# power.net
KiCad netlist of a schematic drawn in Altium Designer
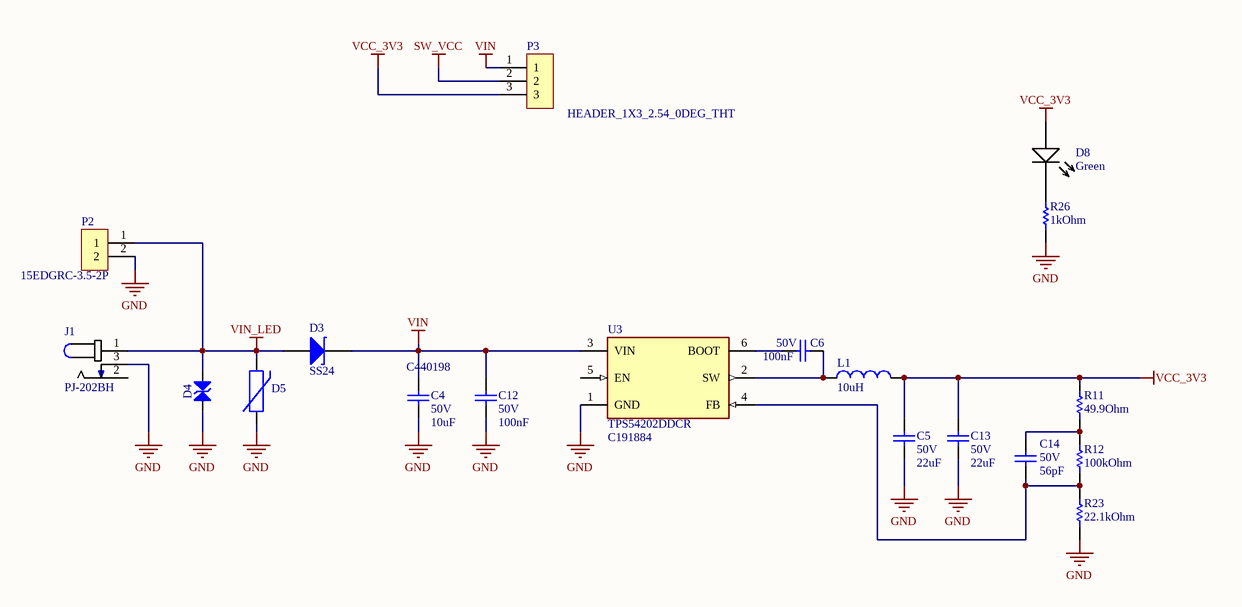
[diagram p0: power.SchDoc]

(export (version "E")
  (design (tool "Eeschema 10.0.6"))
  (components
    (comp (ref "C4")
      (value "10uF 0805 50V")
      (footprint "CAP_0805_High_density")
      (description "Generic Ceramic Capacitor SMD")
      (fields
        (field (name "TOLERANCE") "0%")
        (field (name "VOLTAGE") "50V")
        (field (name "CAPACITANCE") "10uF")
        (field (name "SUPPLIER PART NUMBER 1") "C440198")
      )
      (libsource (lib "MY_LIB") (part "Capacitor SMD_1"))
    )
    (comp (ref "C5")
      (value "22uF 0805 50V")
      (footprint "CAP_0805_High_density")
      (description "Generic Ceramic Capacitor SMD")
      (fields
        (field (name "TOLERANCE") "0%")
        (field (name "VOLTAGE") "50V")
        (field (name "CAPACITANCE") "22uF")
      )
      (libsource (lib "MY_LIB") (part "Capacitor SMD_1"))
    )
    (comp (ref "C6")
      (value "~")
      (footprint "CAP_0603_High_density")
      (description "Generic Ceramic Capacitor SMD")
      (fields
        (field (name "TOLERANCE") "10%")
        (field (name "VOLTAGE") "50V")
        (field (name "CAPACITANCE") "100nF")
      )
      (libsource (lib "altium_conclusive_library") (part "Capacitor SMD"))
    )
    (comp (ref "C12")
      (value "~")
      (footprint "CAP_0603_High_density")
      (description "Generic Ceramic Capacitor SMD")
      (fields
        (field (name "TOLERANCE") "10%")
        (field (name "VOLTAGE") "50V")
        (field (name "CAPACITANCE") "100nF")
      )
      (libsource (lib "altium_conclusive_library") (part "Capacitor SMD"))
    )
    (comp (ref "C13")
      (value "22uF 0805 50V")
      (footprint "CAP_0805_High_density")
      (description "Generic Ceramic Capacitor SMD")
      (fields
        (field (name "TOLERANCE") "0%")
        (field (name "VOLTAGE") "50V")
        (field (name "CAPACITANCE") "22uF")
      )
      (libsource (lib "MY_LIB") (part "Capacitor SMD_1"))
    )
    (comp (ref "C14")
      (value "56pF 0603 50V")
      (footprint "CAP_0603_High_density")
      (description "Generic Ceramic Capacitor SMD")
      (fields
        (field (name "TOLERANCE") "0%")
        (field (name "VOLTAGE") "50V")
        (field (name "CAPACITANCE") "56pF")
      )
      (libsource (lib "MY_LIB") (part "Capacitor SMD_1"))
    )
    (comp (ref "D3")
      (value "SS24")
      (footprint "DO214AA")
      (description "40V Single 500mV@2A 2A DO-214AA Schottky Barrier Diodes (SBD) ROHS")
      (libsource (lib "MY_LIB") (part "Dioda prostownicza Schottky"))
    )
    (comp (ref "D4")
      (value "SMCJ15CA")
      (footprint "DIOM7959X262N")
      (description "24.4V Clamp 61.5A Ipp Tvs Diode Surface Mount DO-214AB (SMCJ)")
      (fields
        (field (name "PART NUMBER") "SMCJ28CA")
        (field (name "VOLTAGE") "28V")
        (field (name "AUTHOR") "CERN DEM JLC")
      )
      (libsource (lib "altium_conclusive_library") (part "SMCJ15CA"))
    )
    (comp (ref "D5")
      (value "C283933")
      (footprint "SIOV-S14K50")
      (description "82V 4.5kA Varistor 1 Circuit Through Hole Disc 14mm")
      (libsource (lib "altium_conclusive_library") (part "B72214S0500K101"))
    )
    (comp (ref "D8")
      (value "C205450")
      (footprint "LED_0603")
      (description "Generic LED diode SMD Green")
      (fields (field (name "COLOUR") "Green"))
      (libsource (lib "MY_LIB") (part "LED diode"))
    )
    (comp (ref "J1")
      (value "PJ-202BH")
      (footprint "CUI_PJ-202BH")
      (description "2.5 x 6.5 mm, 5.0 A, Horizontal, Through Hole, Kinked Pins, Dc Power Jack Connector")
      (libsource (lib "altium_conclusive_library") (part "PJ-202BH"))
    )
    (comp (ref "L1")
      (value "NR8040T100M")
      (footprint "INDP8080X42N")
      (description "10µH Shielded Wirewound Inductor 3.1A 44.2mOhm Max Nonstandard")
      (fields (field (name "INDUCTANCE") "10uH"))
      (libsource (lib "MY_LIB") (part "NR8040T100M"))
    )
    (comp (ref "P2")
      (value "15EDGRC-3.5-2P")
      (footprint "15EDGRC-3.5 - 2 pin")
      (description "15EDGRC-3.5 - 2 pin")
      (libsource (lib "MY_LIB") (part "15EDGRC-3.5-2P"))
    )
    (comp (ref "P3")
      (value "HEADER_1X3_2.54_0DEG_THT")
      (footprint "HDR1X3_2.54")
      (description "3pin 1x3 2.54mm 0.100\" pitch header vertical tht")
      (libsource (lib "MY_LIB") (part "Header 1x3"))
    )
    (comp (ref "R11")
      (value "0603 49.9Ohm 1%")
      (footprint "RES_0603")
      (description "Generic Resistor SMD")
      (fields (field (name "RESISTANCE") "49.9Ohm"))
      (libsource (lib "MY_LIB") (part "Resistor SMD_1"))
    )
    (comp (ref "R12")
      (value "0603 100kOhm 1%")
      (footprint "RES_0603")
      (description "Generic Resistor SMD")
      (fields (field (name "RESISTANCE") "100kOhm"))
      (libsource (lib "MY_LIB") (part "Resistor SMD_1"))
    )
    (comp (ref "R23")
      (value "0603 22.1kOhm 1%")
      (footprint "RES_0603")
      (description "Generic Resistor SMD")
      (fields (field (name "RESISTANCE") "22.1kOhm"))
      (libsource (lib "MY_LIB") (part "Resistor SMD_1"))
    )
    (comp (ref "R26")
      (value "0603 1kOhm 1%")
      (footprint "RES_0603")
      (description "Generic Resistor SMD")
      (fields (field (name "RESISTANCE") "1kOhm"))
      (libsource (lib "MY_LIB") (part "Resistor SMD_1"))
    )
    (comp (ref "U3")
      (value "TPS54202DDCR")
      (footprint "FP-DDC0006A-MFG")
      (description "IC REG BUCK ADJ 2A TSOT23-6")
      (fields (field (name "SUPPLIER PART NUMBER 1") "C191884"))
      (libsource (lib "MY_LIB") (part "TPS54202DDCR"))
    )
  )
  (nets
    (net (code "1") (name "GND") (class "Default")
      (node (ref "C12") (pin "2") (pinfunction "2_2") (pintype "passive"))
      (node (ref "C13") (pin "1") (pinfunction "1_1") (pintype "passive"))
      (node (ref "C4") (pin "1") (pinfunction "1_1") (pintype "passive"))
      (node (ref "C5") (pin "1") (pinfunction "1_1") (pintype "passive"))
      (node (ref "D4") (pin "2") (pinfunction "A_2") (pintype "passive"))
      (node (ref "D5") (pin "1") (pinfunction "1_1") (pintype "passive"))
      (node (ref "J1") (pin "3") (pinfunction "3_3") (pintype "passive"))
      (node (ref "P2") (pin "2") (pinfunction "2_2") (pintype "passive"))
      (node (ref "R23") (pin "2") (pinfunction "2_2") (pintype "passive"))
      (node (ref "R26") (pin "1") (pinfunction "1_1") (pintype "passive"))
      (node (ref "U3") (pin "1") (pinfunction "GND_1") (pintype "power_in"))
    )
    (net (code "2") (name "Net-(C14-Pad2)") (class "Default")
      (node (ref "C14") (pin "2") (pinfunction "2_2") (pintype "passive"))
      (node (ref "R11") (pin "2") (pinfunction "2_2") (pintype "passive"))
      (node (ref "R12") (pin "1") (pinfunction "1_1") (pintype "passive"))
    )
    (net (code "3") (name "Net-(D8-PadC)") (class "Default")
      (node (ref "D8") (pin "C") (pinfunction "C_C") (pintype "passive"))
      (node (ref "R26") (pin "2") (pinfunction "2_2") (pintype "passive"))
    )
    (net (code "4") (name "Net-(U3-BOOT)") (class "Default")
      (node (ref "C6") (pin "1") (pinfunction "1_1") (pintype "passive"))
      (node (ref "U3") (pin "6") (pinfunction "BOOT_6") (pintype "passive"))
    )
    (net (code "5") (name "Net-(U3-FB)") (class "Default")
      (node (ref "C14") (pin "1") (pinfunction "1_1") (pintype "passive"))
      (node (ref "R12") (pin "2") (pinfunction "2_2") (pintype "passive"))
      (node (ref "R23") (pin "1") (pinfunction "1_1") (pintype "passive"))
      (node (ref "U3") (pin "4") (pinfunction "FB_4") (pintype "input"))
    )
    (net (code "6") (name "Net-(U3-SW)") (class "Default")
      (node (ref "C6") (pin "2") (pinfunction "2_2") (pintype "passive"))
      (node (ref "L1") (pin "1") (pinfunction "1_1") (pintype "passive"))
      (node (ref "U3") (pin "2") (pinfunction "SW_2") (pintype "output"))
    )
    (net (code "7") (name "SW_VCC") (class "Default")
      (node (ref "P3") (pin "2") (pinfunction "2_2") (pintype "passive"))
    )
    (net (code "8") (name "VCC_3V3") (class "Default")
      (node (ref "C13") (pin "2") (pinfunction "2_2") (pintype "passive"))
      (node (ref "C5") (pin "2") (pinfunction "2_2") (pintype "passive"))
      (node (ref "D8") (pin "A") (pinfunction "A_A") (pintype "passive"))
      (node (ref "L1") (pin "2") (pinfunction "2_2") (pintype "passive"))
      (node (ref "P3") (pin "3") (pinfunction "3_3") (pintype "passive"))
      (node (ref "R11") (pin "1") (pinfunction "1_1") (pintype "passive"))
    )
    (net (code "9") (name "VIN") (class "Default")
      (node (ref "C12") (pin "1") (pinfunction "1_1") (pintype "passive"))
      (node (ref "C4") (pin "2") (pinfunction "2_2") (pintype "passive"))
      (node (ref "D3") (pin "K") (pinfunction "K_K") (pintype "passive"))
      (node (ref "P3") (pin "1") (pinfunction "1_1") (pintype "passive"))
      (node (ref "U3") (pin "3") (pinfunction "VIN_3") (pintype "power_in"))
    )
    (net (code "10") (name "VIN_LED") (class "Default")
      (node (ref "D3") (pin "A") (pinfunction "A_A") (pintype "passive"))
      (node (ref "D4") (pin "1") (pinfunction "C_1") (pintype "passive"))
      (node (ref "D5") (pin "2") (pinfunction "2_2") (pintype "passive"))
      (node (ref "J1") (pin "1") (pinfunction "1_1") (pintype "passive"))
      (node (ref "P2") (pin "1") (pinfunction "1_1") (pintype "passive"))
    )
    (net (code "11") (name "unconnected-(J1-Pad2)") (class "Default")
      (node (ref "J1") (pin "2") (pinfunction "2_2") (pintype "passive"))
    )
    (net (code "12") (name "unconnected-(U3-EN-Pad5)") (class "Default")
      (node (ref "U3") (pin "5") (pinfunction "EN_5") (pintype "input"))
    )
  )
)
